# baymaxother.net
KiCad netlist of a schematic drawn in Altium Designer
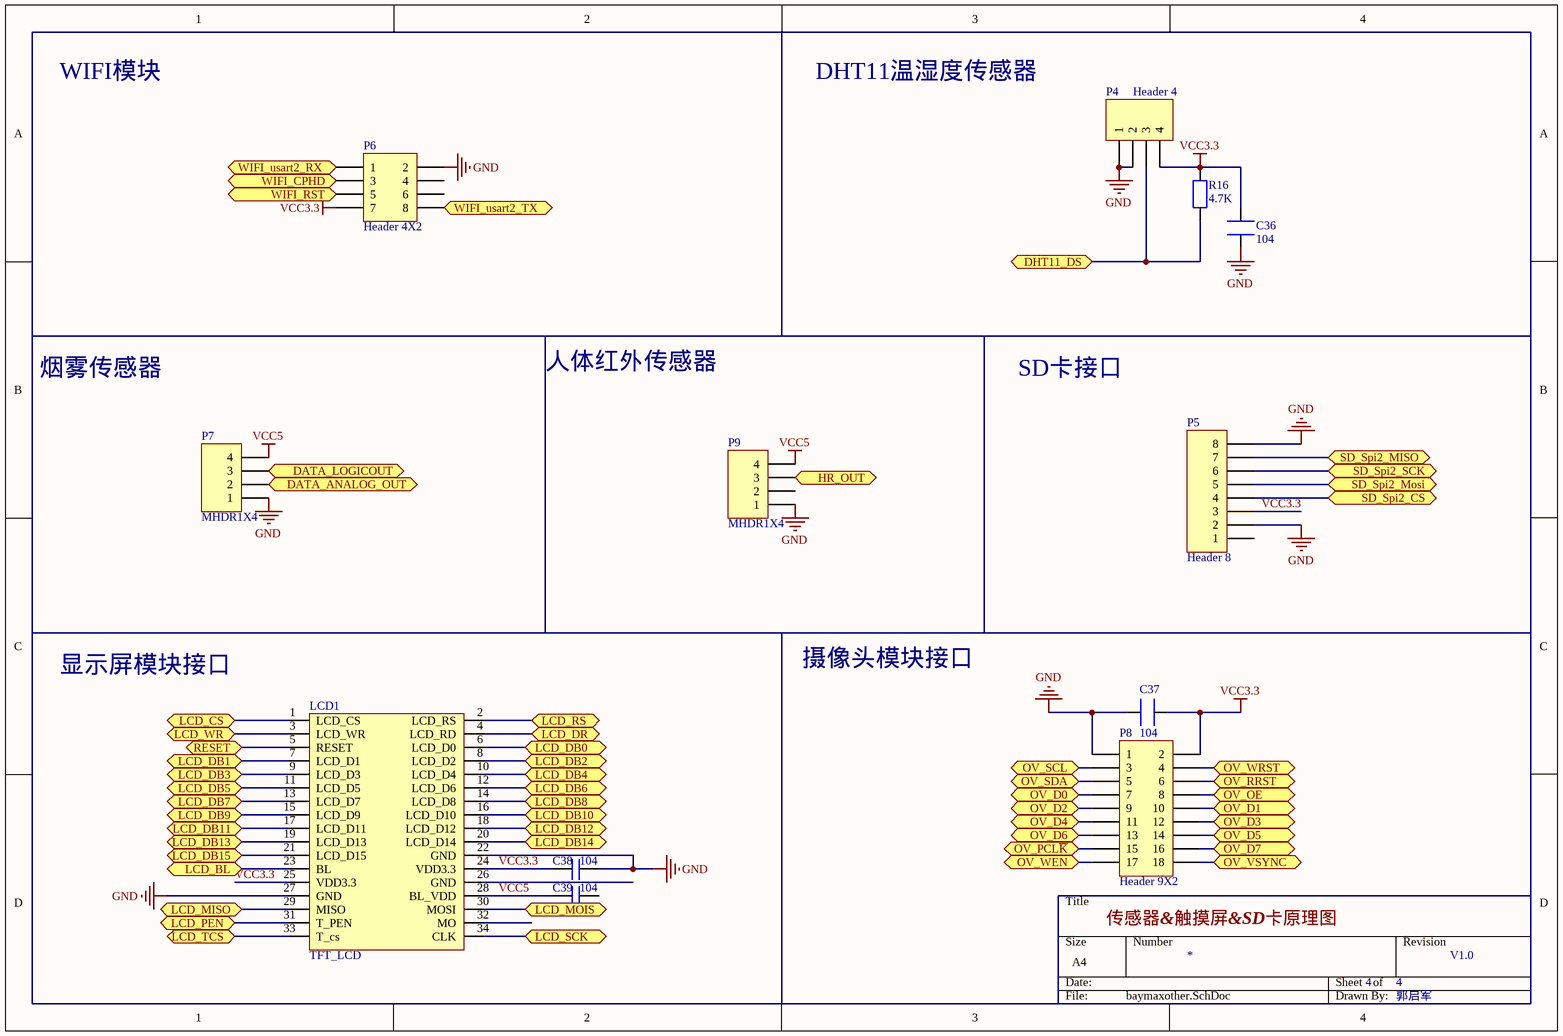
[diagram p0: baymaxother.SchDoc]

(export (version "E")
  (design (tool "Eeschema 10.0.6"))
  (components
    (comp (ref "C36")
      (value "104")
      (footprint "0805-bottom layer")
      (description "电容")
      (libsource (lib "Baymax") (part "104"))
    )
    (comp (ref "C37")
      (value "104")
      (footprint "0805-bottom layer")
      (description "电容")
      (libsource (lib "Baymax") (part "104"))
    )
    (comp (ref "C38") (value "104") (footprint "0805-bottom layer") (libsource (lib "Schlib1") (part "C")))
    (comp (ref "C39") (value "104") (footprint "0805-bottom layer") (libsource (lib "Schlib1") (part "C")))
    (comp (ref "LCD1") (value "TFT_LCD") (footprint "HDR2X17") (libsource (lib "Schlib1") (part "TFT_LCD")))
    (comp (ref "P4")
      (value "Header 4")
      (footprint "HDR1X4")
      (description "Header, 4-Pin")
      (fields (field (name "PUBLISHER") "Altium Limited"))
      (libsource (lib "Miscellaneous Connectors") (part "Header 4"))
    )
    (comp (ref "P5")
      (value "Header 8")
      (footprint "HDR1X8")
      (description "Header, 8-Pin")
      (fields (field (name "PUBLISHER") "Altium Limited"))
      (libsource (lib "Miscellaneous Connectors") (part "Header 8"))
    )
    (comp (ref "P6")
      (value "Header 4X2")
      (footprint "HDR2X4")
      (description "Header, 4-Pin, Dual row")
      (fields (field (name "PUBLISHER") "Altium Limited"))
      (libsource (lib "Miscellaneous Connectors") (part "Header 4X2"))
    )
    (comp (ref "P7")
      (value "MHDR1X4")
      (footprint "MHDR1X4")
      (description "Header, 4-Pin")
      (fields (field (name "PUBLISHER") "Altium Limited"))
      (libsource (lib "Miscellaneous Connectors") (part "MHDR1X4"))
    )
    (comp (ref "P8")
      (value "Header 9X2")
      (footprint "HDR2X9")
      (description "Header, 9-Pin, Dual row")
      (fields (field (name "PUBLISHER") "Altium Limited"))
      (libsource (lib "Miscellaneous Connectors") (part "Header 9X2"))
    )
    (comp (ref "P9")
      (value "MHDR1X4")
      (footprint "MHDR1X4")
      (description "Header, 4-Pin")
      (fields (field (name "PUBLISHER") "Altium Limited"))
      (libsource (lib "Miscellaneous Connectors") (part "MHDR1X4"))
    )
    (comp (ref "R16")
      (value "4.7K")
      (footprint "0805-bottom layer")
      (description "电阻")
      (libsource (lib "Baymax") (part "4.7K"))
    )
  )
  (nets
    (net (code "1") (name "/DATA_ANALOG_OUT") (class "Default")
      (node (ref "P7") (pin "2") (pinfunction "2_2") (pintype "passive"))
    )
    (net (code "2") (name "/DATA_LOGICOUT") (class "Default")
      (node (ref "P7") (pin "3") (pinfunction "3_3") (pintype "passive"))
    )
    (net (code "3") (name "/DHT11_DS") (class "Default")
      (node (ref "P4") (pin "3") (pinfunction "3_3") (pintype "passive"))
      (node (ref "R16") (pin "2") (pintype "passive"))
    )
    (net (code "4") (name "/HR_OUT") (class "Default")
      (node (ref "P9") (pin "3") (pinfunction "3_3") (pintype "passive"))
    )
    (net (code "5") (name "/LCD_BL") (class "Default")
      (node (ref "LCD1") (pin "23") (pinfunction "BL_23") (pintype "passive"))
    )
    (net (code "6") (name "/LCD_CS") (class "Default")
      (node (ref "LCD1") (pin "1") (pinfunction "LCD_CS_1") (pintype "passive"))
    )
    (net (code "7") (name "/LCD_DB0") (class "Default")
      (node (ref "LCD1") (pin "6") (pinfunction "LCD_D0_6") (pintype "passive"))
    )
    (net (code "8") (name "/LCD_DB1") (class "Default")
      (node (ref "LCD1") (pin "7") (pinfunction "LCD_D1_7") (pintype "passive"))
    )
    (net (code "9") (name "/LCD_DB2") (class "Default")
      (node (ref "LCD1") (pin "8") (pinfunction "LCD_D2_8") (pintype "passive"))
    )
    (net (code "10") (name "/LCD_DB3") (class "Default")
      (node (ref "LCD1") (pin "9") (pinfunction "LCD_D3_9") (pintype "passive"))
    )
    (net (code "11") (name "/LCD_DB4") (class "Default")
      (node (ref "LCD1") (pin "10") (pinfunction "LCD_D4_10") (pintype "passive"))
    )
    (net (code "12") (name "/LCD_DB5") (class "Default")
      (node (ref "LCD1") (pin "11") (pinfunction "LCD_D5_11") (pintype "passive"))
    )
    (net (code "13") (name "/LCD_DB6") (class "Default")
      (node (ref "LCD1") (pin "12") (pinfunction "LCD_D6_12") (pintype "passive"))
    )
    (net (code "14") (name "/LCD_DB7") (class "Default")
      (node (ref "LCD1") (pin "13") (pinfunction "LCD_D7_13") (pintype "passive"))
    )
    (net (code "15") (name "/LCD_DB8") (class "Default")
      (node (ref "LCD1") (pin "14") (pinfunction "LCD_D8_14") (pintype "passive"))
    )
    (net (code "16") (name "/LCD_DB9") (class "Default")
      (node (ref "LCD1") (pin "15") (pinfunction "LCD_D9_15") (pintype "passive"))
    )
    (net (code "17") (name "/LCD_DB10") (class "Default")
      (node (ref "LCD1") (pin "16") (pinfunction "LCD_D10_16") (pintype "passive"))
    )
    (net (code "18") (name "/LCD_DB11") (class "Default")
      (node (ref "LCD1") (pin "17") (pinfunction "LCD_D11_17") (pintype "passive"))
    )
    (net (code "19") (name "/LCD_DB12") (class "Default")
      (node (ref "LCD1") (pin "18") (pinfunction "LCD_D12_18") (pintype "passive"))
    )
    (net (code "20") (name "/LCD_DB13") (class "Default")
      (node (ref "LCD1") (pin "19") (pinfunction "LCD_D13_19") (pintype "passive"))
    )
    (net (code "21") (name "/LCD_DB14") (class "Default")
      (node (ref "LCD1") (pin "20") (pinfunction "LCD_D14_20") (pintype "passive"))
    )
    (net (code "22") (name "/LCD_DB15") (class "Default")
      (node (ref "LCD1") (pin "21") (pinfunction "LCD_D15_21") (pintype "passive"))
    )
    (net (code "23") (name "/LCD_DR") (class "Default")
      (node (ref "LCD1") (pin "4") (pinfunction "LCD_RD_4") (pintype "passive"))
    )
    (net (code "24") (name "/LCD_MISO") (class "Default")
      (node (ref "LCD1") (pin "29") (pinfunction "MISO_29") (pintype "passive"))
    )
    (net (code "25") (name "/LCD_MOIS") (class "Default")
      (node (ref "LCD1") (pin "30") (pinfunction "MOSI_30") (pintype "passive"))
    )
    (net (code "26") (name "/LCD_PEN") (class "Default")
      (node (ref "LCD1") (pin "31") (pinfunction "T_PEN_31") (pintype "passive"))
    )
    (net (code "27") (name "/LCD_RS") (class "Default")
      (node (ref "LCD1") (pin "2") (pinfunction "LCD_RS_2") (pintype "passive"))
    )
    (net (code "28") (name "/LCD_SCK") (class "Default")
      (node (ref "LCD1") (pin "34") (pinfunction "CLK_34") (pintype "passive"))
    )
    (net (code "29") (name "/LCD_TCS") (class "Default")
      (node (ref "LCD1") (pin "33") (pinfunction "T_cs_33") (pintype "passive"))
    )
    (net (code "30") (name "/LCD_WR") (class "Default")
      (node (ref "LCD1") (pin "3") (pinfunction "LCD_WR_3") (pintype "passive"))
    )
    (net (code "31") (name "/OV_D0") (class "Default")
      (node (ref "P8") (pin "7") (pinfunction "7_7") (pintype "passive"))
    )
    (net (code "32") (name "/OV_D1") (class "Default")
      (node (ref "P8") (pin "10") (pinfunction "10_10") (pintype "passive"))
    )
    (net (code "33") (name "/OV_D2") (class "Default")
      (node (ref "P8") (pin "9") (pinfunction "9_9") (pintype "passive"))
    )
    (net (code "34") (name "/OV_D3") (class "Default")
      (node (ref "P8") (pin "12") (pinfunction "12_12") (pintype "passive"))
    )
    (net (code "35") (name "/OV_D4") (class "Default")
      (node (ref "P8") (pin "11") (pinfunction "11_11") (pintype "passive"))
    )
    (net (code "36") (name "/OV_D5") (class "Default")
      (node (ref "P8") (pin "14") (pinfunction "14_14") (pintype "passive"))
    )
    (net (code "37") (name "/OV_D6") (class "Default")
      (node (ref "P8") (pin "13") (pinfunction "13_13") (pintype "passive"))
    )
    (net (code "38") (name "/OV_D7") (class "Default")
      (node (ref "P8") (pin "16") (pinfunction "16_16") (pintype "passive"))
    )
    (net (code "39") (name "/OV_OE") (class "Default")
      (node (ref "P8") (pin "8") (pinfunction "8_8") (pintype "passive"))
    )
    (net (code "40") (name "/OV_PCL~{K}") (class "Default")
      (node (ref "P8") (pin "15") (pinfunction "15_15") (pintype "passive"))
    )
    (net (code "41") (name "/OV_RRST") (class "Default")
      (node (ref "P8") (pin "6") (pinfunction "6_6") (pintype "passive"))
    )
    (net (code "42") (name "/OV_SCL") (class "Default")
      (node (ref "P8") (pin "3") (pinfunction "3_3") (pintype "passive"))
    )
    (net (code "43") (name "/OV_SDA") (class "Default")
      (node (ref "P8") (pin "5") (pinfunction "5_5") (pintype "passive"))
    )
    (net (code "44") (name "/OV_VSYNC") (class "Default")
      (node (ref "P8") (pin "18") (pinfunction "18_18") (pintype "passive"))
    )
    (net (code "45") (name "/OV_WEN") (class "Default")
      (node (ref "P8") (pin "17") (pinfunction "17_17") (pintype "passive"))
    )
    (net (code "46") (name "/OV_WRST") (class "Default")
      (node (ref "P8") (pin "4") (pinfunction "4_4") (pintype "passive"))
    )
    (net (code "47") (name "/RESET") (class "Default")
      (node (ref "LCD1") (pin "5") (pinfunction "RESET_5") (pintype "passive"))
    )
    (net (code "48") (name "/SD_Spi2_CS") (class "Default")
      (node (ref "P5") (pin "4") (pinfunction "4_4") (pintype "passive"))
    )
    (net (code "49") (name "/SD_Spi2_MISO") (class "Default")
      (node (ref "P5") (pin "7") (pinfunction "7_7") (pintype "passive"))
    )
    (net (code "50") (name "/SD_Spi2_Mosi") (class "Default")
      (node (ref "P5") (pin "5") (pinfunction "5_5") (pintype "passive"))
    )
    (net (code "51") (name "/SD_Spi2_SCK") (class "Default")
      (node (ref "P5") (pin "6") (pinfunction "6_6") (pintype "passive"))
    )
    (net (code "52") (name "/WIFI_CPHD") (class "Default")
      (node (ref "P6") (pin "3") (pinfunction "3_3") (pintype "passive"))
    )
    (net (code "53") (name "/WIFI_RST") (class "Default")
      (node (ref "P6") (pin "5") (pinfunction "5_5") (pintype "passive"))
    )
    (net (code "54") (name "/WIFI_usart2_RX") (class "Default")
      (node (ref "P6") (pin "1") (pinfunction "1_1") (pintype "passive"))
    )
    (net (code "55") (name "/WIFI_usart2_TX") (class "Default")
      (node (ref "P6") (pin "8") (pinfunction "8_8") (pintype "passive"))
    )
    (net (code "56") (name "GND") (class "Default")
      (node (ref "C36") (pin "2") (pintype "passive"))
      (node (ref "C37") (pin "2") (pintype "passive"))
      (node (ref "C38") (pin "2") (pintype "passive"))
      (node (ref "LCD1") (pin "22") (pinfunction "GND_22") (pintype "passive"))
      (node (ref "LCD1") (pin "27") (pinfunction "GND_27") (pintype "passive"))
      (node (ref "P4") (pin "1") (pinfunction "1_1") (pintype "passive"))
      (node (ref "P4") (pin "2") (pinfunction "2_2") (pintype "passive"))
      (node (ref "P5") (pin "2") (pinfunction "2_2") (pintype "passive"))
      (node (ref "P5") (pin "8") (pinfunction "8_8") (pintype "passive"))
      (node (ref "P6") (pin "2") (pinfunction "2_2") (pintype "passive"))
      (node (ref "P7") (pin "1") (pinfunction "1_1") (pintype "passive"))
      (node (ref "P8") (pin "1") (pinfunction "1_1") (pintype "passive"))
      (node (ref "P9") (pin "1") (pinfunction "1_1") (pintype "passive"))
    )
    (net (code "57") (name "VCC3.3") (class "Default")
      (node (ref "C36") (pin "1") (pintype "passive"))
      (node (ref "C37") (pin "1") (pintype "passive"))
      (node (ref "C38") (pin "1") (pintype "passive"))
      (node (ref "LCD1") (pin "24") (pinfunction "VDD3.3_24") (pintype "passive"))
      (node (ref "LCD1") (pin "25") (pinfunction "VDD3.3_25") (pintype "passive"))
      (node (ref "P4") (pin "4") (pinfunction "4_4") (pintype "passive"))
      (node (ref "P5") (pin "3") (pinfunction "3_3") (pintype "passive"))
      (node (ref "P6") (pin "7") (pinfunction "7_7") (pintype "passive"))
      (node (ref "P8") (pin "2") (pinfunction "2_2") (pintype "passive"))
      (node (ref "R16") (pin "1") (pintype "passive"))
    )
    (net (code "58") (name "VCC5") (class "Default")
      (node (ref "C39") (pin "1") (pintype "passive"))
      (node (ref "LCD1") (pin "28") (pinfunction "BL_VDD_28") (pintype "passive"))
      (node (ref "P7") (pin "4") (pinfunction "4_4") (pintype "passive"))
      (node (ref "P9") (pin "4") (pinfunction "4_4") (pintype "passive"))
    )
    (net (code "59") (name "unconnected-(C39-Pad2)") (class "Default")
      (node (ref "C39") (pin "2") (pintype "passive"))
    )
    (net (code "60") (name "unconnected-(LCD1-GND-Pad26)") (class "Default")
      (node (ref "LCD1") (pin "26") (pinfunction "GND_26") (pintype "passive"))
    )
    (net (code "61") (name "unconnected-(LCD1-MO-Pad32)") (class "Default")
      (node (ref "LCD1") (pin "32") (pinfunction "MO_32") (pintype "passive"))
    )
    (net (code "62") (name "unconnected-(P5-Pad1)") (class "Default")
      (node (ref "P5") (pin "1") (pinfunction "1_1") (pintype "passive"))
    )
    (net (code "63") (name "unconnected-(P6-Pad4)") (class "Default")
      (node (ref "P6") (pin "4") (pinfunction "4_4") (pintype "passive"))
    )
    (net (code "64") (name "unconnected-(P6-Pad6)") (class "Default")
      (node (ref "P6") (pin "6") (pinfunction "6_6") (pintype "passive"))
    )
    (net (code "65") (name "unconnected-(P9-Pad2)") (class "Default")
      (node (ref "P9") (pin "2") (pinfunction "2_2") (pintype "passive"))
    )
  )
)
